# ESP8266_MQTT_light.net
KiCad netlist of a schematic drawn in EAGLE
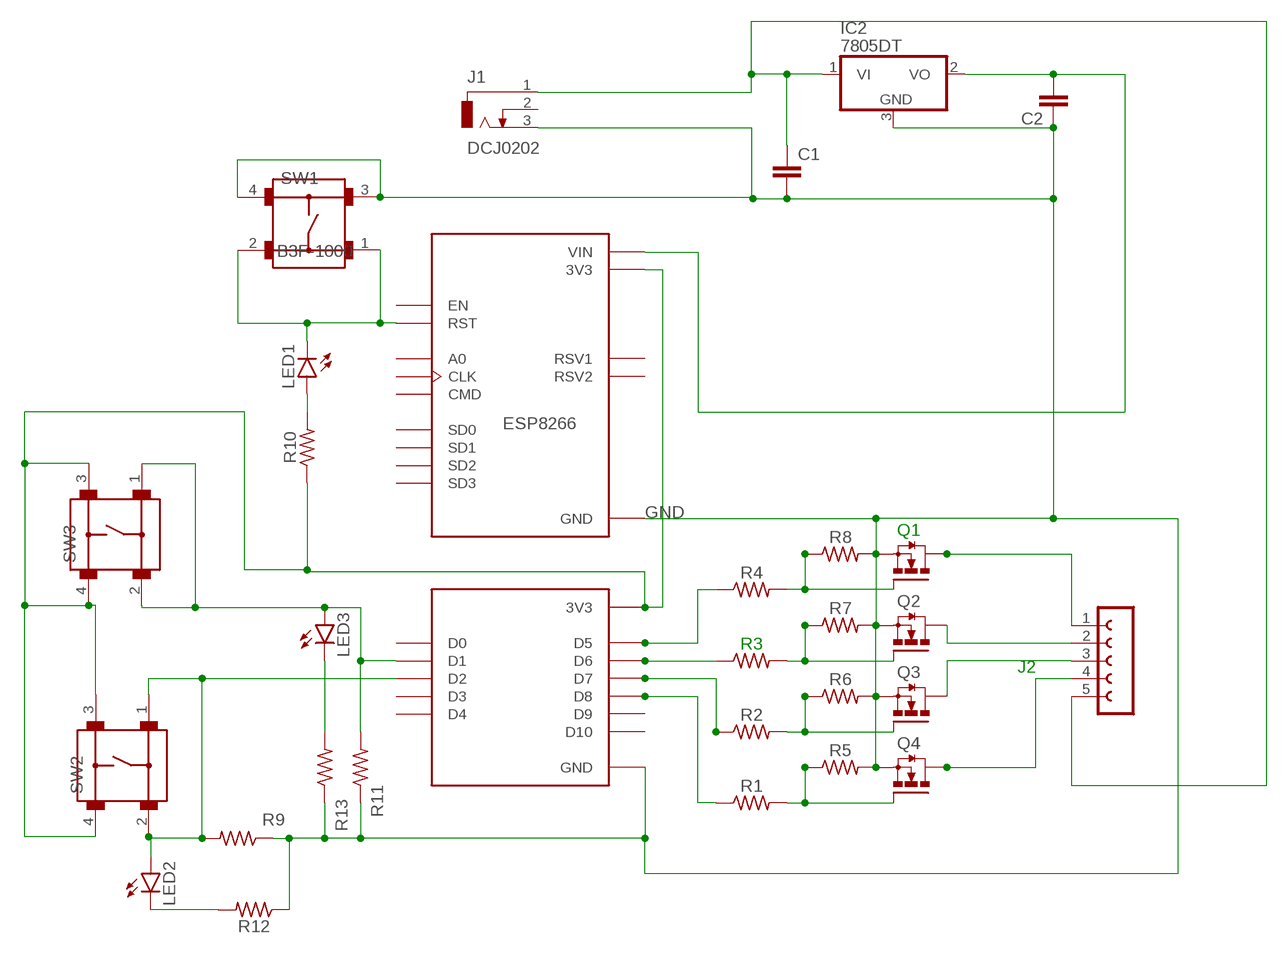
[diagram p0: schematic, sheet 1]

(export (version "E")
  (design (tool "Eeschema 10.0.6"))
  (components
    (comp (ref "C1")
      (value "CC1005")
      (footprint "eagle-import:C1005")
      (libsource (lib "eagle-import") (part "CC1005"))
    )
    (comp (ref "C2")
      (value "CC1005")
      (footprint "eagle-import:C1005")
      (libsource (lib "eagle-import") (part "CC1005"))
    )
    (comp (ref "ESP8266")
      (value "113990105")
      (footprint "eagle-import:SEEED_113990105")
      (fields (field (name "MF") "Seeed Technology") (field (name "MP") "NodeMCU v2"))
      (libsource (lib "eagle-import") (part "113990105"))
    )
    (comp (ref "IC2")
      (value "7805DT")
      (footprint "eagle-import:TO252")
      (libsource (lib "eagle-import") (part "78DT05"))
    )
    (comp (ref "J1")
      (value "DCJ0202")
      (footprint "eagle-import:DCJ0202")
      (libsource (lib "eagle-import") (part "DCJ0202"))
    )
    (comp (ref "J2")
      (value "RGBW1")
      (footprint "eagle-import:FE05W")
      (libsource (lib "eagle-import") (part "FE05W"))
    )
    (comp (ref "LED1")
      (value "LEDCHIPLED_1206")
      (footprint "eagle-import:CHIPLED_1206")
      (libsource (lib "eagle-import") (part "LEDCHIPLED_1206"))
    )
    (comp (ref "LED2")
      (value "LEDCHIPLED_1206")
      (footprint "eagle-import:CHIPLED_1206")
      (libsource (lib "eagle-import") (part "LEDCHIPLED_1206"))
    )
    (comp (ref "LED3")
      (value "LEDCHIPLED_1206")
      (footprint "eagle-import:CHIPLED_1206")
      (libsource (lib "eagle-import") (part "LEDCHIPLED_1206"))
    )
    (comp (ref "Q1")
      (value "IRF3704S")
      (footprint "eagle-import:D2PACK")
      (libsource (lib "eagle-import") (part "IRF3704S"))
    )
    (comp (ref "Q2")
      (value "IRF3704S")
      (footprint "eagle-import:D2PACK")
      (libsource (lib "eagle-import") (part "IRF3704S"))
    )
    (comp (ref "Q3")
      (value "IRF3704S")
      (footprint "eagle-import:D2PACK")
      (libsource (lib "eagle-import") (part "IRF3704S"))
    )
    (comp (ref "Q4")
      (value "IRF3704S")
      (footprint "eagle-import:D2PACK")
      (libsource (lib "eagle-import") (part "IRF3704S"))
    )
    (comp (ref "R1")
      (value "1k")
      (footprint "eagle-import:R1206")
      (libsource (lib "eagle-import") (part "R-US_R1206"))
    )
    (comp (ref "R2")
      (value "1k")
      (footprint "eagle-import:R1206")
      (libsource (lib "eagle-import") (part "R-US_R1206"))
    )
    (comp (ref "R3")
      (value "1k")
      (footprint "eagle-import:R1206")
      (libsource (lib "eagle-import") (part "R-US_R1206"))
    )
    (comp (ref "R4")
      (value "1k")
      (footprint "eagle-import:R1206")
      (libsource (lib "eagle-import") (part "R-US_R1206"))
    )
    (comp (ref "R5")
      (value "10k")
      (footprint "eagle-import:R1206")
      (libsource (lib "eagle-import") (part "R-US_R1206"))
    )
    (comp (ref "R6")
      (value "10k")
      (footprint "eagle-import:R1206")
      (libsource (lib "eagle-import") (part "R-US_R1206"))
    )
    (comp (ref "R7")
      (value "10k")
      (footprint "eagle-import:R1206")
      (libsource (lib "eagle-import") (part "R-US_R1206"))
    )
    (comp (ref "R8")
      (value "10k")
      (footprint "eagle-import:R1206")
      (libsource (lib "eagle-import") (part "R-US_R1206"))
    )
    (comp (ref "R9")
      (value "10k")
      (footprint "eagle-import:R1206")
      (libsource (lib "eagle-import") (part "R-US_R1206"))
    )
    (comp (ref "R10")
      (value "33")
      (footprint "eagle-import:R1206")
      (libsource (lib "eagle-import") (part "R-US_R1206"))
    )
    (comp (ref "R11")
      (value "10k")
      (footprint "eagle-import:R1206")
      (libsource (lib "eagle-import") (part "R-US_R1206"))
    )
    (comp (ref "R12")
      (value "33")
      (footprint "eagle-import:R1206")
      (libsource (lib "eagle-import") (part "R-US_R1206"))
    )
    (comp (ref "R13")
      (value "33")
      (footprint "eagle-import:R1206")
      (libsource (lib "eagle-import") (part "R-US_R1206"))
    )
    (comp (ref "SW1")
      (value "B3F-1000")
      (footprint "eagle-import:B3F-1000")
      (fields
        (field (name "DIGI_KEY_PART_NUMBER") "SW400-ND")
        (field (name "MANUFACTURER") "Omron Electronics Inc-EMC Div")
        (field (name "CREATED_BY") "PCBLayout.com")
      )
      (libsource (lib "eagle-import") (part "B3F-1000"))
    )
    (comp (ref "SW2")
      (value "B3F-1000")
      (footprint "eagle-import:B3F-1000")
      (fields
        (field (name "DIGI_KEY_PART_NUMBER") "SW400-ND")
        (field (name "MANUFACTURER") "Omron Electronics Inc-EMC Div")
        (field (name "CREATED_BY") "PCBLayout.com")
      )
      (libsource (lib "eagle-import") (part "B3F-1000"))
    )
    (comp (ref "SW3")
      (value "B3F-1000")
      (footprint "eagle-import:B3F-1000")
      (fields
        (field (name "DIGI_KEY_PART_NUMBER") "SW400-ND")
        (field (name "MANUFACTURER") "Omron Electronics Inc-EMC Div")
        (field (name "CREATED_BY") "PCBLayout.com")
      )
      (libsource (lib "eagle-import") (part "B3F-1000"))
    )
  )
  (nets
    (net (code "1") (name "/GND") (class "Default")
      (node (ref "C1") (pin "2") (pinfunction "2_2") (pintype "passive"))
      (node (ref "C2") (pin "1") (pinfunction "1_1") (pintype "passive"))
      (node (ref "ESP8266") (pin "J1_10") (pinfunction "GND_J1_10") (pintype "power_in"))
      (node (ref "ESP8266") (pin "J1_14") (pinfunction "GND_J1_14") (pintype "power_in"))
      (node (ref "ESP8266") (pin "J2_14") (pinfunction "GND_J2_14") (pintype "power_in"))
      (node (ref "ESP8266") (pin "J2_7") (pinfunction "GND_J2_7") (pintype "power_in"))
      (node (ref "IC2") (pin "3") (pinfunction "GND_3") (pintype "passive"))
      (node (ref "J1") (pin "3") (pinfunction "3_3") (pintype "passive"))
      (node (ref "Q1") (pin "3") (pinfunction "S_3") (pintype "passive"))
      (node (ref "Q2") (pin "3") (pinfunction "S_3") (pintype "passive"))
      (node (ref "Q3") (pin "3") (pinfunction "S_3") (pintype "passive"))
      (node (ref "Q4") (pin "3") (pinfunction "S_3") (pintype "passive"))
      (node (ref "R11") (pin "1") (pinfunction "1_1") (pintype "passive"))
      (node (ref "R12") (pin "1") (pinfunction "1_1") (pintype "passive"))
      (node (ref "R13") (pin "1") (pinfunction "1_1") (pintype "passive"))
      (node (ref "R5") (pin "2") (pinfunction "2_2") (pintype "passive"))
      (node (ref "R6") (pin "2") (pinfunction "2_2") (pintype "passive"))
      (node (ref "R7") (pin "2") (pinfunction "2_2") (pintype "passive"))
      (node (ref "R8") (pin "2") (pinfunction "2_2") (pintype "passive"))
      (node (ref "R9") (pin "1") (pinfunction "1_1") (pintype "passive"))
      (node (ref "SW1") (pin "3") (pinfunction "3_3") (pintype "passive"))
      (node (ref "SW1") (pin "4") (pinfunction "4_4") (pintype "passive"))
    )
    (net (code "2") (name "Net-(ESP8266A-3V3)") (class "Default")
      (node (ref "ESP8266") (pin "J1_11") (pinfunction "3V3_J1_11") (pintype "power_in"))
      (node (ref "ESP8266") (pin "J2_15") (pinfunction "3V3_J2_15") (pintype "power_in"))
      (node (ref "ESP8266") (pin "J2_6") (pinfunction "3V3_J2_6") (pintype "power_in"))
      (node (ref "R10") (pin "1") (pinfunction "1_1") (pintype "passive"))
      (node (ref "SW2") (pin "3") (pinfunction "3_3") (pintype "passive"))
      (node (ref "SW2") (pin "4") (pinfunction "4_4") (pintype "passive"))
      (node (ref "SW3") (pin "3") (pinfunction "3_3") (pintype "passive"))
      (node (ref "SW3") (pin "4") (pinfunction "4_4") (pintype "passive"))
    )
    (net (code "3") (name "Net-(ESP8266A-RST)") (class "Default")
      (node (ref "ESP8266") (pin "J1_13") (pinfunction "RST_J1_13") (pintype "input"))
      (node (ref "LED1") (pin "C") (pinfunction "C_C") (pintype "passive"))
      (node (ref "SW1") (pin "1") (pinfunction "1_1") (pintype "passive"))
      (node (ref "SW1") (pin "2") (pinfunction "2_2") (pintype "passive"))
    )
    (net (code "4") (name "Net-(ESP8266A-VIN)") (class "Default")
      (node (ref "C2") (pin "2") (pinfunction "2_2") (pintype "passive"))
      (node (ref "ESP8266") (pin "J1_15") (pinfunction "VIN_J1_15") (pintype "power_in"))
      (node (ref "IC2") (pin "2") (pinfunction "VO_2") (pintype "passive"))
    )
    (net (code "5") (name "Net-(ESP8266B-D1)") (class "Default")
      (node (ref "ESP8266") (pin "J2_2") (pinfunction "D1_J2_2") (pintype "bidirectional"))
      (node (ref "LED3") (pin "A") (pinfunction "A_A") (pintype "passive"))
      (node (ref "R11") (pin "2") (pinfunction "2_2") (pintype "passive"))
      (node (ref "SW3") (pin "1") (pinfunction "1_1") (pintype "passive"))
      (node (ref "SW3") (pin "2") (pinfunction "2_2") (pintype "passive"))
    )
    (net (code "6") (name "Net-(ESP8266B-D2)") (class "Default")
      (node (ref "ESP8266") (pin "J2_3") (pinfunction "D2_J2_3") (pintype "bidirectional"))
      (node (ref "LED2") (pin "A") (pinfunction "A_A") (pintype "passive"))
      (node (ref "R9") (pin "2") (pinfunction "2_2") (pintype "passive"))
      (node (ref "SW2") (pin "1") (pinfunction "1_1") (pintype "passive"))
      (node (ref "SW2") (pin "2") (pinfunction "2_2") (pintype "passive"))
    )
    (net (code "7") (name "Net-(ESP8266B-D5)") (class "Default")
      (node (ref "ESP8266") (pin "J2_8") (pinfunction "D5_J2_8") (pintype "bidirectional"))
      (node (ref "R4") (pin "1") (pinfunction "1_1") (pintype "passive"))
    )
    (net (code "8") (name "Net-(ESP8266B-D6)") (class "Default")
      (node (ref "ESP8266") (pin "J2_9") (pinfunction "D6_J2_9") (pintype "bidirectional"))
      (node (ref "R3") (pin "1") (pinfunction "1_1") (pintype "passive"))
    )
    (net (code "9") (name "Net-(ESP8266B-D7)") (class "Default")
      (node (ref "ESP8266") (pin "J2_10") (pinfunction "D7_J2_10") (pintype "bidirectional"))
      (node (ref "R2") (pin "1") (pinfunction "1_1") (pintype "passive"))
    )
    (net (code "10") (name "Net-(ESP8266B-D8)") (class "Default")
      (node (ref "ESP8266") (pin "J2_11") (pinfunction "D8_J2_11") (pintype "bidirectional"))
      (node (ref "R1") (pin "1") (pinfunction "1_1") (pintype "passive"))
    )
    (net (code "11") (name "Net-(IC2-VI)") (class "Default")
      (node (ref "C1") (pin "1") (pinfunction "1_1") (pintype "passive"))
      (node (ref "IC2") (pin "1") (pinfunction "VI_1") (pintype "input"))
      (node (ref "J1") (pin "1") (pinfunction "1_1") (pintype "passive"))
      (node (ref "J2") (pin "5") (pinfunction "5_5") (pintype "passive"))
    )
    (net (code "12") (name "Net-(LED1-PadA)") (class "Default")
      (node (ref "LED1") (pin "A") (pinfunction "A_A") (pintype "passive"))
      (node (ref "R10") (pin "2") (pinfunction "2_2") (pintype "passive"))
    )
    (net (code "13") (name "Net-(LED2-PadC)") (class "Default")
      (node (ref "LED2") (pin "C") (pinfunction "C_C") (pintype "passive"))
      (node (ref "R12") (pin "2") (pinfunction "2_2") (pintype "passive"))
    )
    (net (code "14") (name "Net-(LED3-PadC)") (class "Default")
      (node (ref "LED3") (pin "C") (pinfunction "C_C") (pintype "passive"))
      (node (ref "R13") (pin "2") (pinfunction "2_2") (pintype "passive"))
    )
    (net (code "15") (name "Net-(Q1-D)") (class "Default")
      (node (ref "J2") (pin "1") (pinfunction "1_1") (pintype "passive"))
      (node (ref "Q1") (pin "2") (pinfunction "D_2") (pintype "passive"))
    )
    (net (code "16") (name "Net-(Q1-G)") (class "Default")
      (node (ref "Q1") (pin "1") (pinfunction "G_1") (pintype "passive"))
      (node (ref "R4") (pin "2") (pinfunction "2_2") (pintype "passive"))
      (node (ref "R8") (pin "1") (pinfunction "1_1") (pintype "passive"))
    )
    (net (code "17") (name "Net-(Q2-D)") (class "Default")
      (node (ref "J2") (pin "2") (pinfunction "2_2") (pintype "passive"))
      (node (ref "Q2") (pin "2") (pinfunction "D_2") (pintype "passive"))
    )
    (net (code "18") (name "Net-(Q2-G)") (class "Default")
      (node (ref "Q2") (pin "1") (pinfunction "G_1") (pintype "passive"))
      (node (ref "R3") (pin "2") (pinfunction "2_2") (pintype "passive"))
      (node (ref "R7") (pin "1") (pinfunction "1_1") (pintype "passive"))
    )
    (net (code "19") (name "Net-(Q3-D)") (class "Default")
      (node (ref "J2") (pin "3") (pinfunction "3_3") (pintype "passive"))
      (node (ref "Q3") (pin "2") (pinfunction "D_2") (pintype "passive"))
    )
    (net (code "20") (name "Net-(Q3-G)") (class "Default")
      (node (ref "Q3") (pin "1") (pinfunction "G_1") (pintype "passive"))
      (node (ref "R2") (pin "2") (pinfunction "2_2") (pintype "passive"))
      (node (ref "R6") (pin "1") (pinfunction "1_1") (pintype "passive"))
    )
    (net (code "21") (name "Net-(Q4-D)") (class "Default")
      (node (ref "J2") (pin "4") (pinfunction "4_4") (pintype "passive"))
      (node (ref "Q4") (pin "2") (pinfunction "D_2") (pintype "passive"))
    )
    (net (code "22") (name "Net-(Q4-G)") (class "Default")
      (node (ref "Q4") (pin "1") (pinfunction "G_1") (pintype "passive"))
      (node (ref "R1") (pin "2") (pinfunction "2_2") (pintype "passive"))
      (node (ref "R5") (pin "1") (pinfunction "1_1") (pintype "passive"))
    )
    (net (code "23") (name "unconnected-(ESP8266A-A0-PadJ1_1)") (class "Default")
      (node (ref "ESP8266") (pin "J1_1") (pinfunction "A0_J1_1") (pintype "bidirectional"))
    )
    (net (code "24") (name "unconnected-(ESP8266A-CLK-PadJ1_9)") (class "Default")
      (node (ref "ESP8266") (pin "J1_9") (pinfunction "CLK_J1_9") (pintype "bidirectional"))
    )
    (net (code "25") (name "unconnected-(ESP8266A-CMD-PadJ1_7)") (class "Default")
      (node (ref "ESP8266") (pin "J1_7") (pinfunction "CMD_J1_7") (pintype "bidirectional"))
    )
    (net (code "26") (name "unconnected-(ESP8266A-EN-PadJ1_12)") (class "Default")
      (node (ref "ESP8266") (pin "J1_12") (pinfunction "EN_J1_12") (pintype "input"))
    )
    (net (code "27") (name "unconnected-(ESP8266A-RSV1-PadJ1_2)") (class "Default")
      (node (ref "ESP8266") (pin "J1_2") (pinfunction "RSV1_J1_2") (pintype "bidirectional"))
    )
    (net (code "28") (name "unconnected-(ESP8266A-RSV2-PadJ1_3)") (class "Default")
      (node (ref "ESP8266") (pin "J1_3") (pinfunction "RSV2_J1_3") (pintype "bidirectional"))
    )
    (net (code "29") (name "unconnected-(ESP8266A-SD0-PadJ1_8)") (class "Default")
      (node (ref "ESP8266") (pin "J1_8") (pinfunction "SD0_J1_8") (pintype "bidirectional"))
    )
    (net (code "30") (name "unconnected-(ESP8266A-SD1-PadJ1_6)") (class "Default")
      (node (ref "ESP8266") (pin "J1_6") (pinfunction "SD1_J1_6") (pintype "bidirectional"))
    )
    (net (code "31") (name "unconnected-(ESP8266A-SD2-PadJ1_5)") (class "Default")
      (node (ref "ESP8266") (pin "J1_5") (pinfunction "SD2_J1_5") (pintype "bidirectional"))
    )
    (net (code "32") (name "unconnected-(ESP8266A-SD3-PadJ1_4)") (class "Default")
      (node (ref "ESP8266") (pin "J1_4") (pinfunction "SD3_J1_4") (pintype "bidirectional"))
    )
    (net (code "33") (name "unconnected-(ESP8266B-D0-PadJ2_1)") (class "Default")
      (node (ref "ESP8266") (pin "J2_1") (pinfunction "D0_J2_1") (pintype "bidirectional"))
    )
    (net (code "34") (name "unconnected-(ESP8266B-D3-PadJ2_4)") (class "Default")
      (node (ref "ESP8266") (pin "J2_4") (pinfunction "D3_J2_4") (pintype "bidirectional"))
    )
    (net (code "35") (name "unconnected-(ESP8266B-D4-PadJ2_5)") (class "Default")
      (node (ref "ESP8266") (pin "J2_5") (pinfunction "D4_J2_5") (pintype "bidirectional"))
    )
    (net (code "36") (name "unconnected-(ESP8266B-D9-PadJ2_12)") (class "Default")
      (node (ref "ESP8266") (pin "J2_12") (pinfunction "D9_J2_12") (pintype "bidirectional"))
    )
    (net (code "37") (name "unconnected-(ESP8266B-D10-PadJ2_13)") (class "Default")
      (node (ref "ESP8266") (pin "J2_13") (pinfunction "D10_J2_13") (pintype "bidirectional"))
    )
    (net (code "38") (name "unconnected-(J1-Pad2)") (class "Default")
      (node (ref "J1") (pin "2") (pinfunction "2_2") (pintype "passive"))
    )
  )
)
